# SD_Card.net
KiCad netlist of a schematic drawn in Altium Designer
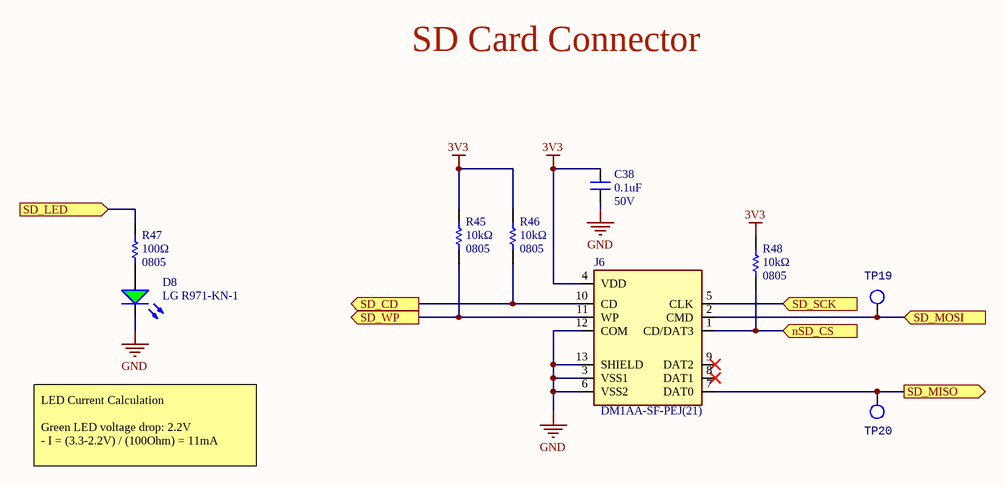
[diagram p0: SD Card.SchDoc]

(export (version "E")
  (design (tool "Eeschema 10.0.6"))
  (components
    (comp (ref "C38")
      (value "0.1uF")
      (footprint "CAPC2012X140N")
      (description "CAP CER 0.1UF 50V X7R 0805")
      (fields
        (field (name "TOLERANCE") "10%")
        (field (name "VOLTAGE RATING") "50V")
        (field (name "Comment") "CAP_0.1uF_50V_0805")
      )
      (libsource (lib "UWRT_Schematic_Library_2020") (part "CAP_0.1uF_50V_0805"))
    )
    (comp (ref "D8")
      (value "DIO_LED_G")
      (footprint "LED_0805_LINE")
      (description "LED GREEN DIFFUSED 0805 SMD")
      (fields (field (name "MANUFACTURER PART NUMBER 1") "LG R971-KN-1"))
      (libsource (lib "UWRT_Schematic_Library_2020") (part "DIO_LED_G"))
    )
    (comp (ref "J6")
      (value "SD_CARD_CON")
      (footprint "HRS_DM1AA-SF-PEJ(21)")
      (description "12 _9 + 3_ Position Card Connector Secure Digital - SD Surface Mount, Right Angle Gold")
      (fields (field (name "MANUFACTURER PART NUMBER 1") "DM1AA-SF-PEJ(21)"))
      (libsource (lib "UWRT_Schematic_Library_2020") (part "SD_CARD_CON"))
    )
    (comp (ref "R45")
      (value "10kΩ")
      (footprint "RESC2012X60N")
      (description "RES SMD 10K OHM 1% 1/8W 0805")
      (fields
        (field (name "CASE CODE (IMPERIAL)") "0805")
        (field (name "TOLERANCE") "1%")
        (field (name "Comment") "RES_10kΩ_0805")
      )
      (libsource (lib "UWRT_Schematic_Library_2020") (part "RES_10kΩ_0805"))
    )
    (comp (ref "R46")
      (value "10kΩ")
      (footprint "RESC2012X60N")
      (description "RES SMD 10K OHM 1% 1/8W 0805")
      (fields
        (field (name "CASE CODE (IMPERIAL)") "0805")
        (field (name "TOLERANCE") "1%")
        (field (name "Comment") "RES_10kΩ_0805")
      )
      (libsource (lib "UWRT_Schematic_Library_2020") (part "RES_10kΩ_0805"))
    )
    (comp (ref "R47")
      (value "100Ω")
      (footprint "RESC2012X60N")
      (description "RES SMD 100 OHM 1% 1/8W 0805")
      (fields (field (name "CASE CODE (IMPERIAL)") "0805") (field (name "Comment") "RES_100Ω_0805"))
      (libsource (lib "UWRT_Schematic_Library_2020") (part "RES_100Ω_0805"))
    )
    (comp (ref "R48")
      (value "10kΩ")
      (footprint "RESC2012X60N")
      (description "RES SMD 10K OHM 1% 1/8W 0805")
      (fields
        (field (name "CASE CODE (IMPERIAL)") "0805")
        (field (name "TOLERANCE") "1%")
        (field (name "Comment") "RES_10kΩ_0805")
      )
      (libsource (lib "UWRT_Schematic_Library_2020") (part "RES_10kΩ_0805"))
    )
    (comp (ref "TP19")
      (value "TESTPOINT_LOOP")
      (footprint "TESTPOINT_LOOP")
      (description "Loop testpoint through-hole pad")
      (libsource (lib "UWRT_Schematic_Library_2020") (part "TESTPOINT_LOOP"))
    )
    (comp (ref "TP20")
      (value "TESTPOINT_LOOP")
      (footprint "TESTPOINT_LOOP")
      (description "Loop testpoint through-hole pad")
      (libsource (lib "UWRT_Schematic_Library_2020") (part "TESTPOINT_LOOP"))
    )
  )
  (nets
    (net (code "1") (name "/SD_CD") (class "Default")
      (node (ref "J6") (pin "10") (pinfunction "CD_10") (pintype "passive"))
      (node (ref "R46") (pin "1") (pinfunction "1_1") (pintype "passive"))
    )
    (net (code "2") (name "/SD_LED") (class "Default")
      (node (ref "R47") (pin "2") (pinfunction "2_2") (pintype "passive"))
    )
    (net (code "3") (name "/SD_MISO") (class "Default")
      (node (ref "J6") (pin "7") (pinfunction "DAT0_7") (pintype "passive"))
      (node (ref "TP20") (pin "1") (pintype "passive"))
    )
    (net (code "4") (name "/SD_MOSI") (class "Default")
      (node (ref "J6") (pin "2") (pinfunction "CMD_2") (pintype "passive"))
      (node (ref "TP19") (pin "1") (pintype "passive"))
    )
    (net (code "5") (name "/SD_SCK") (class "Default")
      (node (ref "J6") (pin "5") (pinfunction "CLK_5") (pintype "passive"))
    )
    (net (code "6") (name "/SD_WP") (class "Default")
      (node (ref "J6") (pin "11") (pinfunction "WP_11") (pintype "passive"))
      (node (ref "R45") (pin "1") (pinfunction "1_1") (pintype "passive"))
    )
    (net (code "7") (name "/nSD_CS") (class "Default")
      (node (ref "J6") (pin "1") (pinfunction "CD/DAT3_1") (pintype "passive"))
      (node (ref "R48") (pin "1") (pinfunction "1_1") (pintype "passive"))
    )
    (net (code "8") (name "3V3") (class "Default")
      (node (ref "C38") (pin "2") (pinfunction "2_2") (pintype "passive"))
      (node (ref "J6") (pin "4") (pinfunction "VDD_4") (pintype "power_in"))
      (node (ref "R45") (pin "2") (pinfunction "2_2") (pintype "passive"))
      (node (ref "R46") (pin "2") (pinfunction "2_2") (pintype "passive"))
      (node (ref "R48") (pin "2") (pinfunction "2_2") (pintype "passive"))
    )
    (net (code "9") (name "GND") (class "Default")
      (node (ref "C38") (pin "1") (pinfunction "1_1") (pintype "passive"))
      (node (ref "D8") (pin "2") (pinfunction "K_2") (pintype "passive"))
      (node (ref "J6") (pin "12") (pinfunction "COM_12") (pintype "passive"))
      (node (ref "J6") (pin "13") (pinfunction "SHIELD_13") (pintype "passive"))
      (node (ref "J6") (pin "3") (pinfunction "VSS1_3") (pintype "power_in"))
      (node (ref "J6") (pin "6") (pinfunction "VSS2_6") (pintype "power_in"))
    )
    (net (code "10") (name "Net-(D8-A)") (class "Default")
      (node (ref "D8") (pin "1") (pinfunction "A_1") (pintype "passive"))
      (node (ref "R47") (pin "1") (pinfunction "1_1") (pintype "passive"))
    )
    (net (code "11") (name "unconnected-(J6-DAT1-Pad8)") (class "Default")
      (node (ref "J6") (pin "8") (pinfunction "DAT1_8") (pintype "passive+no_connect"))
    )
    (net (code "12") (name "unconnected-(J6-DAT2-Pad9)") (class "Default")
      (node (ref "J6") (pin "9") (pinfunction "DAT2_9") (pintype "passive+no_connect"))
    )
  )
)
